# Debug_Interface.net
KiCad netlist of a schematic drawn in Altium Designer
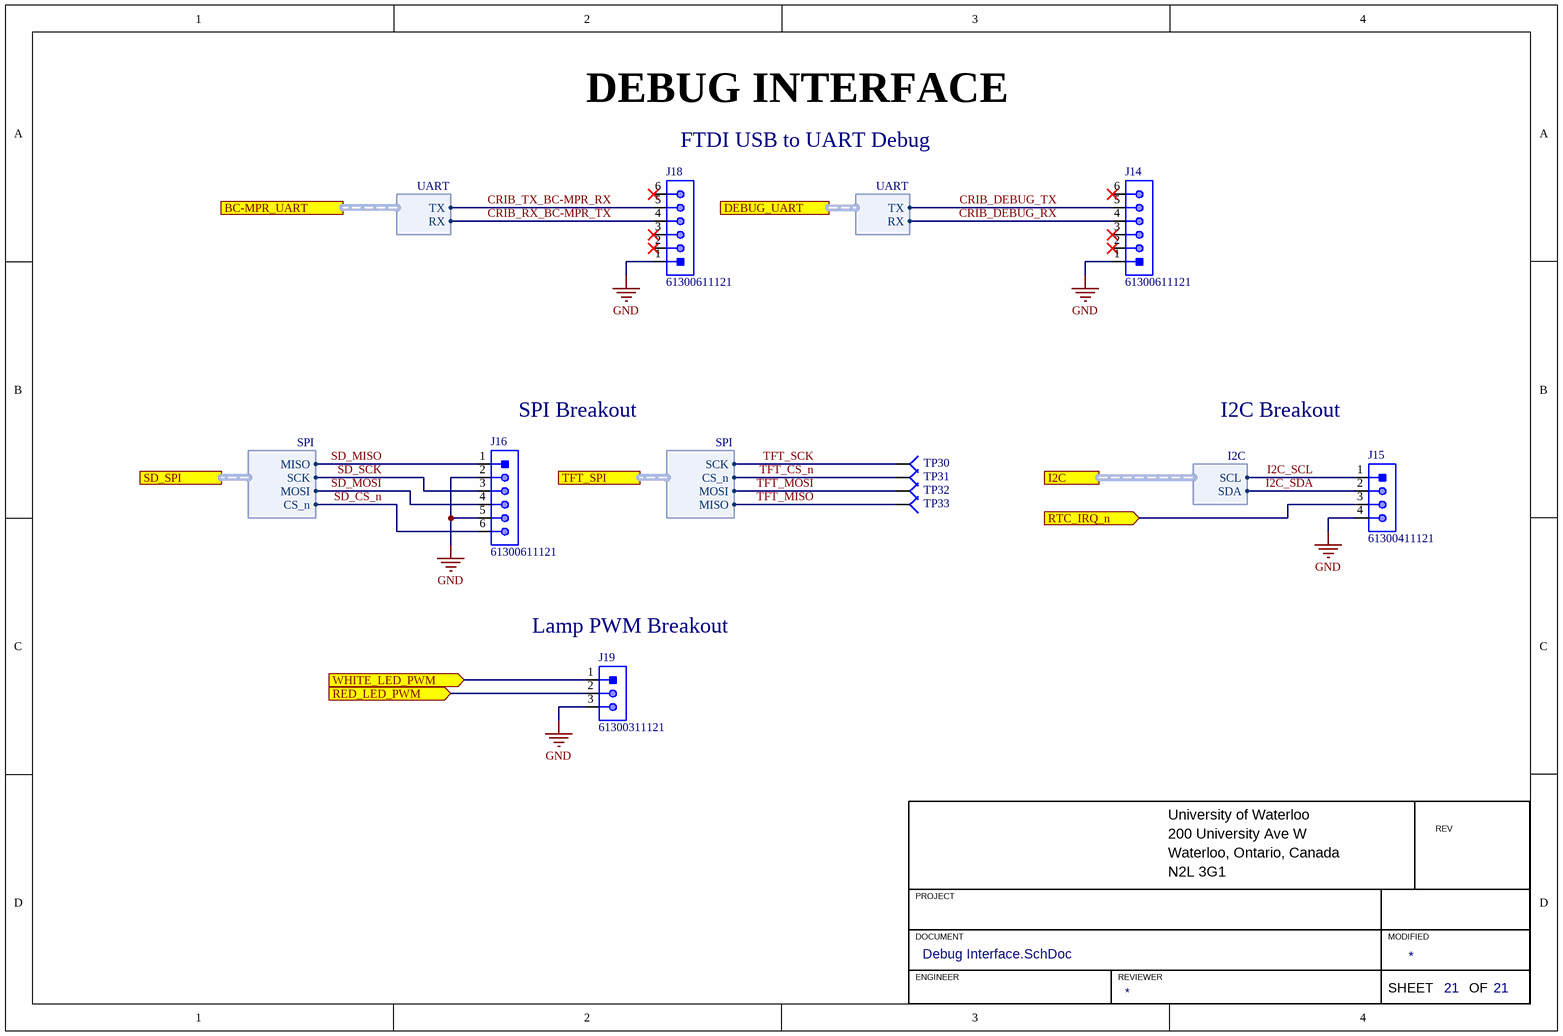
[diagram p0: Debug Interface.SchDoc]

(export (version "E")
  (design (tool "Eeschema 10.0.6"))
  (components
    (comp (ref "J14")
      (value "HEADER 6x1")
      (footprint "HDR1X6")
      (description "CONN HEADER VERT 6POS 2.54MM")
      (fields (field (name "MANUFACTURER PART NUMBER 1") "61300611121"))
      (libsource (lib "Personal_Schematic_Library_2022") (part "HEADER 6x1"))
    )
    (comp (ref "J15")
      (value "HEADER 4x1")
      (footprint "HDR1X4")
      (description "CONN HEADER VERT 4POS 2.54MM")
      (fields (field (name "MANUFACTURER PART NUMBER 1") "61300411121"))
      (libsource (lib "Personal_Schematic_Library_2022") (part "HEADER 4x1"))
    )
    (comp (ref "J16")
      (value "HEADER 6x1")
      (footprint "HDR1X6")
      (description "CONN HEADER VERT 6POS 2.54MM")
      (fields (field (name "MANUFACTURER PART NUMBER 1") "61300611121"))
      (libsource (lib "") (part "HEADER 6x1_1"))
    )
    (comp (ref "J18")
      (value "HEADER 6x1")
      (footprint "HDR1X6")
      (description "CONN HEADER VERT 6POS 2.54MM")
      (fields (field (name "MANUFACTURER PART NUMBER 1") "61300611121"))
      (libsource (lib "Personal_Schematic_Library_2022") (part "HEADER 6x1"))
    )
    (comp (ref "J19")
      (value "HEADER 3x1")
      (footprint "HDR1X3")
      (description "CONN HEADER VERT 3POS 2.54MM")
      (fields (field (name "MANUFACTURER PART NUMBER 1") "61300311121"))
      (libsource (lib "Personal_Schematic_Library_2022") (part "HEADER 3x1"))
    )
    (comp (ref "TP30")
      (value "TESTPOINT_1MM_CIRCLE")
      (footprint "TESTPOINT_CIRCLE_1MM")
      (description "TESTPOINT 1MM CIRCLE")
      (libsource (lib "Personal_Schematic_Library_2022") (part "TESTPOINT_1MM_CIRCLE"))
    )
    (comp (ref "TP31")
      (value "TESTPOINT_1MM_CIRCLE")
      (footprint "TESTPOINT_CIRCLE_1MM")
      (description "TESTPOINT 1MM CIRCLE")
      (libsource (lib "Personal_Schematic_Library_2022") (part "TESTPOINT_1MM_CIRCLE"))
    )
    (comp (ref "TP32")
      (value "TESTPOINT_1MM_CIRCLE")
      (footprint "TESTPOINT_CIRCLE_1MM")
      (description "TESTPOINT 1MM CIRCLE")
      (libsource (lib "Personal_Schematic_Library_2022") (part "TESTPOINT_1MM_CIRCLE"))
    )
    (comp (ref "TP33")
      (value "TESTPOINT_1MM_CIRCLE")
      (footprint "TESTPOINT_CIRCLE_1MM")
      (description "TESTPOINT 1MM CIRCLE")
      (libsource (lib "Personal_Schematic_Library_2022") (part "TESTPOINT_1MM_CIRCLE"))
    )
  )
  (nets
    (net (code "4") (name "/CRIB_DEBUG_RX") (class "Default")
      (node (ref "J14") (pin "4") (pinfunction "4_4") (pintype "passive"))
    )
    (net (code "5") (name "/CRIB_DEBUG_TX") (class "Default")
      (node (ref "J14") (pin "5") (pinfunction "5_5") (pintype "passive"))
    )
    (net (code "6") (name "/CRIB_RX_BC-MPR_TX") (class "Default")
      (node (ref "J18") (pin "4") (pinfunction "4_4") (pintype "passive"))
    )
    (net (code "7") (name "/CRIB_TX_BC-MPR_RX") (class "Default")
      (node (ref "J18") (pin "5") (pinfunction "5_5") (pintype "passive"))
    )
    (net (code "8") (name "/I2C_SCL") (class "Default")
      (node (ref "J15") (pin "1") (pinfunction "1_1") (pintype "passive"))
    )
    (net (code "9") (name "/I2C_SDA") (class "Default")
      (node (ref "J15") (pin "2") (pinfunction "2_2") (pintype "passive"))
    )
    (net (code "10") (name "/RED_LED_PWM") (class "Default")
      (node (ref "J19") (pin "2") (pinfunction "2_2") (pintype "passive"))
    )
    (net (code "11") (name "/RTC_IRQ_n") (class "Default")
      (node (ref "J15") (pin "3") (pinfunction "3_3") (pintype "passive"))
    )
    (net (code "12") (name "/SD_CS_n") (class "Default")
      (node (ref "J16") (pin "6") (pinfunction "6_6") (pintype "passive"))
    )
    (net (code "13") (name "/SD_MISO") (class "Default")
      (node (ref "J16") (pin "1") (pinfunction "1_1") (pintype "passive"))
    )
    (net (code "14") (name "/SD_MOSI") (class "Default")
      (node (ref "J16") (pin "4") (pinfunction "4_4") (pintype "passive"))
    )
    (net (code "15") (name "/SD_SCK") (class "Default")
      (node (ref "J16") (pin "3") (pinfunction "3_3") (pintype "passive"))
    )
    (net (code "16") (name "/TFT_CS_n") (class "Default")
      (node (ref "TP31") (pin "1") (pinfunction "=value_1") (pintype "passive"))
    )
    (net (code "17") (name "/TFT_MISO") (class "Default")
      (node (ref "TP33") (pin "1") (pinfunction "=value_1") (pintype "passive"))
    )
    (net (code "18") (name "/TFT_MOSI") (class "Default")
      (node (ref "TP32") (pin "1") (pinfunction "=value_1") (pintype "passive"))
    )
    (net (code "19") (name "/TFT_SCK") (class "Default")
      (node (ref "TP30") (pin "1") (pinfunction "=value_1") (pintype "passive"))
    )
    (net (code "20") (name "/WHITE_LED_PWM") (class "Default")
      (node (ref "J19") (pin "1") (pinfunction "1_1") (pintype "passive"))
    )
    (net (code "24") (name "GND") (class "Default")
      (node (ref "J14") (pin "1") (pinfunction "1_1") (pintype "passive"))
      (node (ref "J15") (pin "4") (pinfunction "4_4") (pintype "passive"))
      (node (ref "J16") (pin "2") (pinfunction "2_2") (pintype "passive"))
      (node (ref "J16") (pin "5") (pinfunction "5_5") (pintype "passive"))
      (node (ref "J18") (pin "1") (pinfunction "1_1") (pintype "passive"))
      (node (ref "J19") (pin "3") (pinfunction "3_3") (pintype "passive"))
    )
    (net (code "25") (name "unconnected-(J14-Pad2)") (class "Default")
      (node (ref "J14") (pin "2") (pinfunction "2_2") (pintype "passive+no_connect"))
    )
    (net (code "26") (name "unconnected-(J14-Pad3)") (class "Default")
      (node (ref "J14") (pin "3") (pinfunction "3_3") (pintype "passive+no_connect"))
    )
    (net (code "27") (name "unconnected-(J14-Pad6)") (class "Default")
      (node (ref "J14") (pin "6") (pinfunction "6_6") (pintype "passive+no_connect"))
    )
    (net (code "28") (name "unconnected-(J18-Pad2)") (class "Default")
      (node (ref "J18") (pin "2") (pinfunction "2_2") (pintype "passive+no_connect"))
    )
    (net (code "29") (name "unconnected-(J18-Pad3)") (class "Default")
      (node (ref "J18") (pin "3") (pinfunction "3_3") (pintype "passive+no_connect"))
    )
    (net (code "30") (name "unconnected-(J18-Pad6)") (class "Default")
      (node (ref "J18") (pin "6") (pinfunction "6_6") (pintype "passive+no_connect"))
    )
  )
)
